# FW2-02-DingDongDoorbell.net
KiCad netlist of a schematic drawn in EAGLE
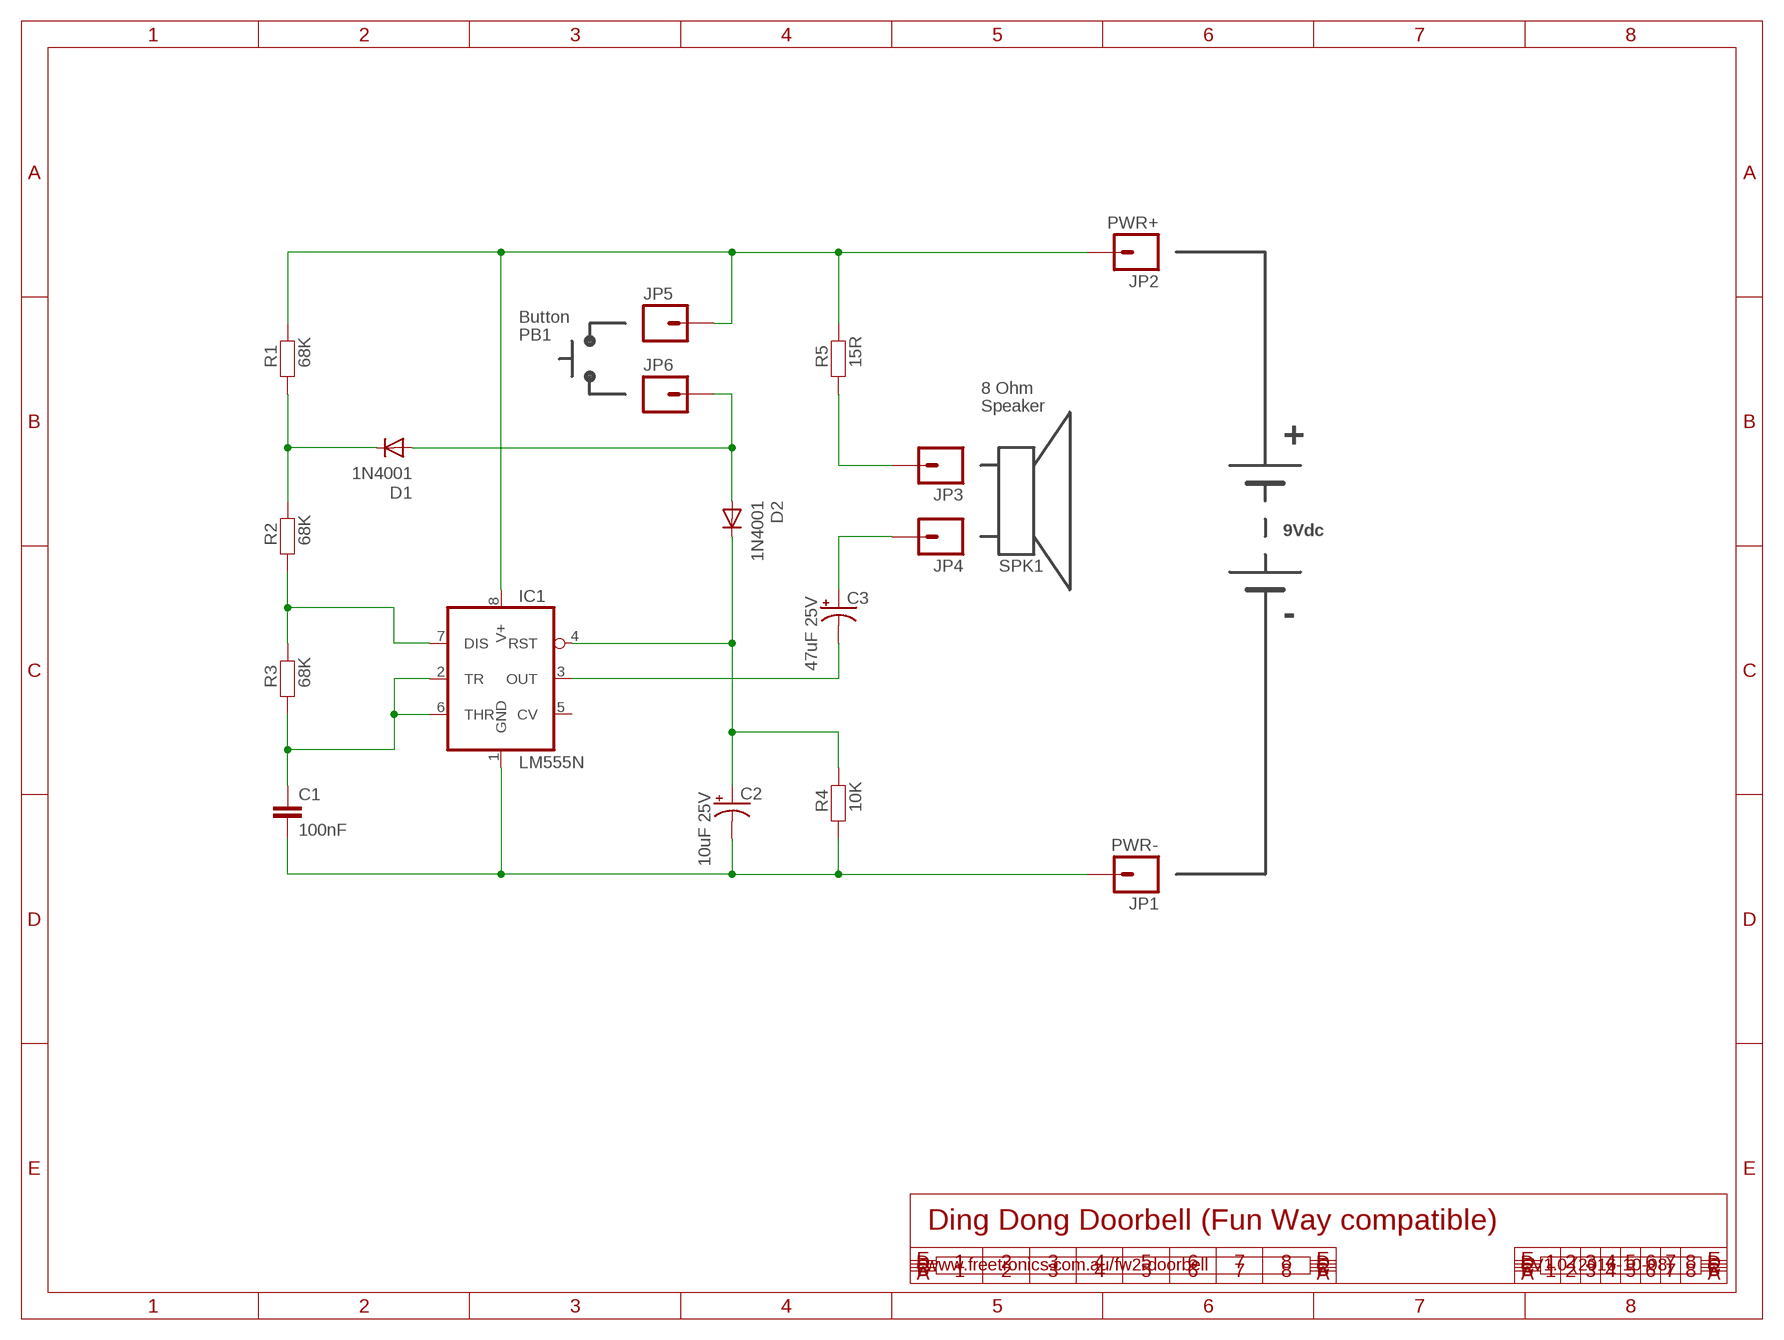
[diagram p0: schematic, sheet 1]

(export (version "E")
  (design (tool "Eeschema 10.0.6"))
  (components
    (comp (ref "C1")
      (value "100nF")
      (footprint "eagle-import:CAP-PTH-SMALL")
      (libsource (lib "eagle-import") (part "CAPPTH"))
    )
    (comp (ref "C2")
      (value "10uF 25V")
      (footprint "eagle-import:CPOL-RADIAL-10UF-25V")
      (libsource (lib "eagle-import") (part "CAP_POLPTH2"))
    )
    (comp (ref "C3")
      (value "47uF 25V")
      (footprint "eagle-import:CPOL-RADIAL-10UF-25V")
      (libsource (lib "eagle-import") (part "CAP_POLPTH2"))
    )
    (comp (ref "D1")
      (value "1N4001")
      (footprint "eagle-import:DIODE-1N4001")
      (libsource (lib "eagle-import") (part "DIODEPTH"))
    )
    (comp (ref "D2")
      (value "1N4001")
      (footprint "eagle-import:DIODE-1N4001")
      (libsource (lib "eagle-import") (part "DIODEPTH"))
    )
    (comp (ref "IC1")
      (value "LM555N")
      (footprint "eagle-import:DIL08")
      (libsource (lib "eagle-import") (part "555NLM"))
    )
    (comp (ref "JP1")
      (value "PWR-")
      (footprint "eagle-import:1X01")
      (libsource (lib "eagle-import") (part "M01PTH"))
    )
    (comp (ref "JP2")
      (value "PWR+")
      (footprint "eagle-import:1X01")
      (libsource (lib "eagle-import") (part "M01PTH"))
    )
    (comp (ref "JP3")
      (value "SPKR+")
      (footprint "eagle-import:1X01")
      (libsource (lib "eagle-import") (part "M01PTH"))
    )
    (comp (ref "JP4")
      (value "SPKR-")
      (footprint "eagle-import:1X01")
      (libsource (lib "eagle-import") (part "M01PTH"))
    )
    (comp (ref "JP5")
      (value "PWR-")
      (footprint "eagle-import:1X01")
      (libsource (lib "eagle-import") (part "M01PTH"))
    )
    (comp (ref "JP6")
      (value "PWR-")
      (footprint "eagle-import:1X01")
      (libsource (lib "eagle-import") (part "M01PTH"))
    )
    (comp (ref "R1")
      (value "68K")
      (footprint "eagle-import:FREETRONICS_AXIAL-0.4")
      (libsource (lib "eagle-import") (part "FREETRONICS_RESISTORPTH2"))
    )
    (comp (ref "R2")
      (value "68K")
      (footprint "eagle-import:FREETRONICS_AXIAL-0.4")
      (libsource (lib "eagle-import") (part "FREETRONICS_RESISTORPTH2"))
    )
    (comp (ref "R3")
      (value "68K")
      (footprint "eagle-import:FREETRONICS_AXIAL-0.4")
      (libsource (lib "eagle-import") (part "FREETRONICS_RESISTORPTH2"))
    )
    (comp (ref "R4")
      (value "10K")
      (footprint "eagle-import:FREETRONICS_AXIAL-0.4")
      (libsource (lib "eagle-import") (part "FREETRONICS_RESISTORPTH2"))
    )
    (comp (ref "R5")
      (value "15R")
      (footprint "eagle-import:FREETRONICS_AXIAL-0.4")
      (libsource (lib "eagle-import") (part "FREETRONICS_RESISTORPTH2"))
    )
  )
  (nets
    (net (code "1") (name "Net-(C2-+)") (class "Default")
      (node (ref "C2") (pin "1") (pinfunction "+_1") (pintype "passive"))
      (node (ref "D2") (pin "C") (pinfunction "C_C") (pintype "passive"))
      (node (ref "IC1") (pin "4") (pinfunction "RST_4") (pintype "input"))
      (node (ref "R4") (pin "P$2") (pinfunction "2_P$2") (pintype "passive"))
    )
    (net (code "2") (name "Net-(C2--)") (class "Default")
      (node (ref "C1") (pin "2") (pinfunction "2_2") (pintype "passive"))
      (node (ref "C2") (pin "2") (pinfunction "-_2") (pintype "passive"))
      (node (ref "IC1") (pin "1") (pinfunction "GND_1") (pintype "power_in"))
      (node (ref "JP1") (pin "1") (pinfunction "1_1") (pintype "passive"))
      (node (ref "R4") (pin "P$1") (pinfunction "1_P$1") (pintype "passive"))
    )
    (net (code "3") (name "Net-(C3-+)") (class "Default")
      (node (ref "C3") (pin "1") (pinfunction "+_1") (pintype "passive"))
      (node (ref "JP4") (pin "1") (pinfunction "1_1") (pintype "passive"))
    )
    (net (code "4") (name "Net-(C3--)") (class "Default")
      (node (ref "C3") (pin "2") (pinfunction "-_2") (pintype "passive"))
      (node (ref "IC1") (pin "3") (pinfunction "OUT_3") (pintype "output"))
    )
    (net (code "5") (name "Net-(D1-PadA)") (class "Default")
      (node (ref "D1") (pin "A") (pinfunction "A_A") (pintype "passive"))
      (node (ref "D2") (pin "A") (pinfunction "A_A") (pintype "passive"))
      (node (ref "JP6") (pin "1") (pinfunction "1_1") (pintype "passive"))
    )
    (net (code "6") (name "Net-(IC1-DIS)") (class "Default")
      (node (ref "IC1") (pin "7") (pinfunction "DIS_7") (pintype "input"))
      (node (ref "R2") (pin "P$1") (pinfunction "1_P$1") (pintype "passive"))
      (node (ref "R3") (pin "P$2") (pinfunction "2_P$2") (pintype "passive"))
    )
    (net (code "7") (name "Net-(IC1-THR)") (class "Default")
      (node (ref "C1") (pin "1") (pinfunction "1_1") (pintype "passive"))
      (node (ref "IC1") (pin "2") (pinfunction "TR_2") (pintype "input"))
      (node (ref "IC1") (pin "6") (pinfunction "THR_6") (pintype "input"))
      (node (ref "R3") (pin "P$1") (pinfunction "1_P$1") (pintype "passive"))
    )
    (net (code "8") (name "Net-(IC1-V+)") (class "Default")
      (node (ref "IC1") (pin "8") (pinfunction "V+_8") (pintype "power_in"))
      (node (ref "JP2") (pin "1") (pinfunction "1_1") (pintype "passive"))
      (node (ref "JP5") (pin "1") (pinfunction "1_1") (pintype "passive"))
      (node (ref "R1") (pin "P$2") (pinfunction "2_P$2") (pintype "passive"))
      (node (ref "R5") (pin "P$2") (pinfunction "2_P$2") (pintype "passive"))
    )
    (net (code "9") (name "Net-(R1-1)") (class "Default")
      (node (ref "D1") (pin "C") (pinfunction "C_C") (pintype "passive"))
      (node (ref "R1") (pin "P$1") (pinfunction "1_P$1") (pintype "passive"))
      (node (ref "R2") (pin "P$2") (pinfunction "2_P$2") (pintype "passive"))
    )
    (net (code "10") (name "Net-(R5-1)") (class "Default")
      (node (ref "JP3") (pin "1") (pinfunction "1_1") (pintype "passive"))
      (node (ref "R5") (pin "P$1") (pinfunction "1_P$1") (pintype "passive"))
    )
    (net (code "11") (name "unconnected-(IC1-CV-Pad5)") (class "Default")
      (node (ref "IC1") (pin "5") (pinfunction "CV_5") (pintype "input"))
    )
  )
)
